# ProPrj_microcontroler_2025-12-02.net
KiCad netlist of a schematic drawn in EasyEDA Pro
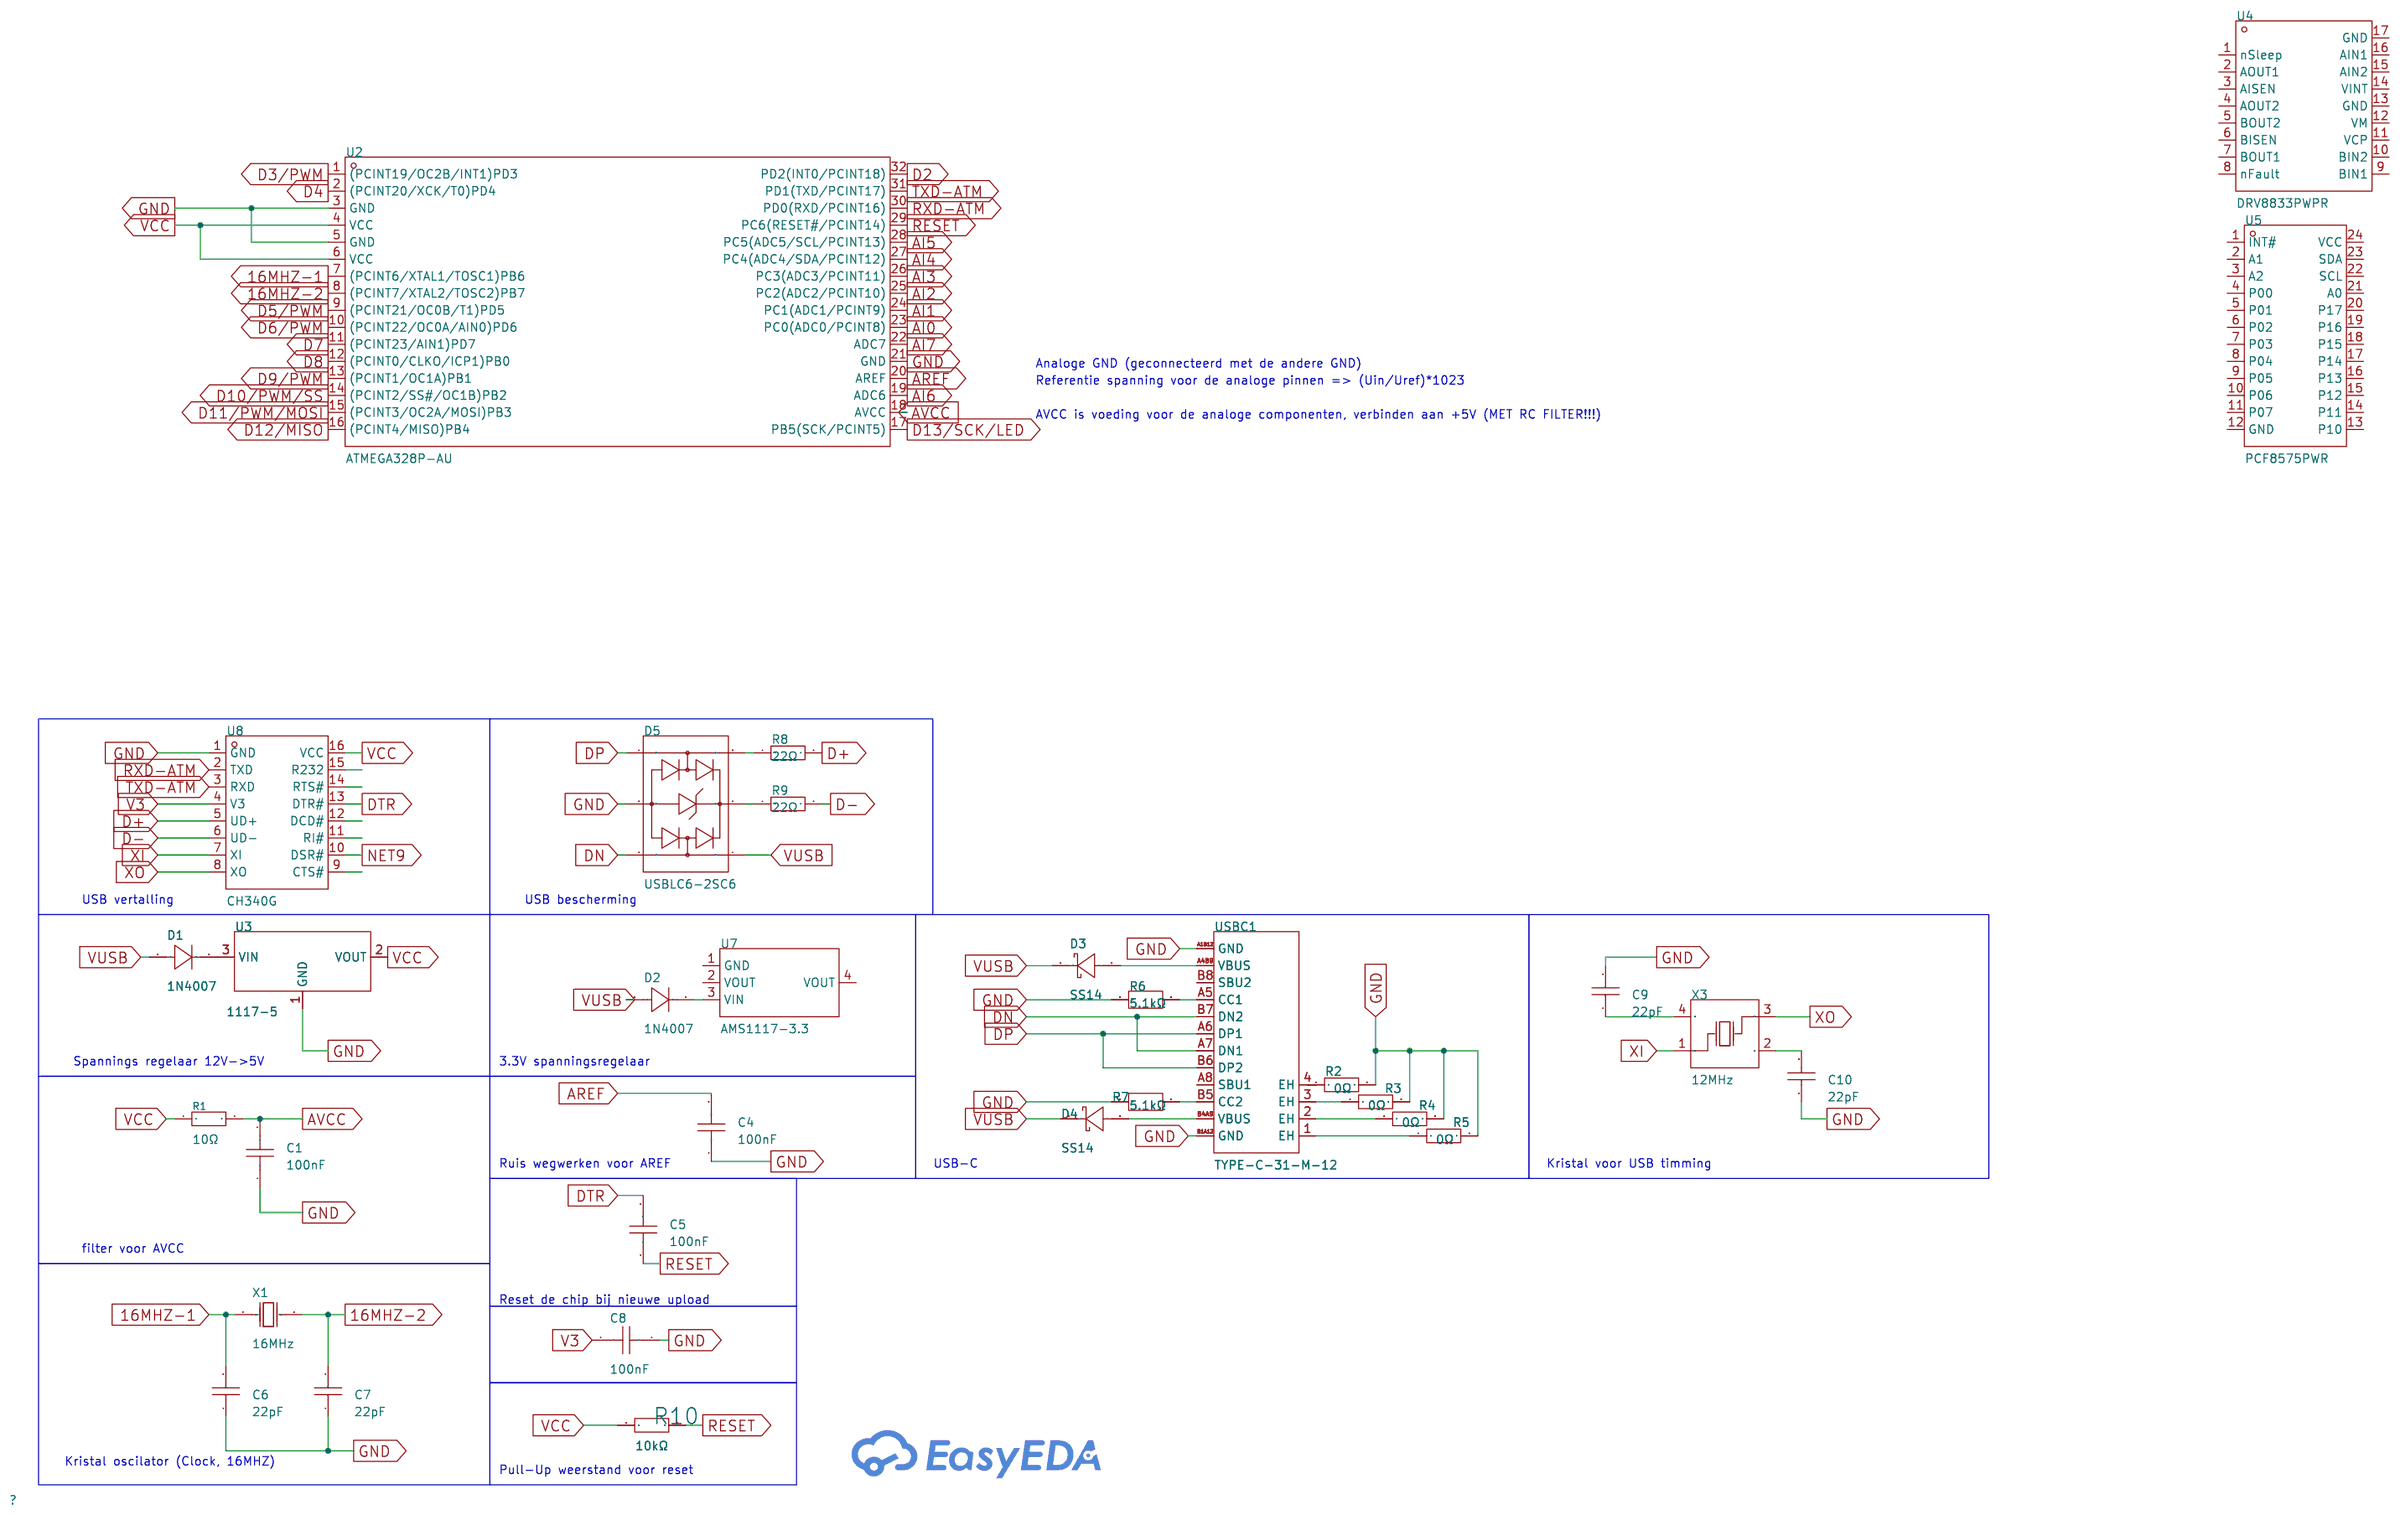
[diagram p0: schematic sheet]

(export (version "E")
  (design (tool "Eeschema 10.0.6"))
  (components
    (comp (ref "C1")
      (value "100nF")
      (footprint "easyedapro:C0603")
      (description "Capacitance:100nF Tolerance:±10% Tolerance:±10% Voltage Rating:50V Temperature Coefficient:X7R")
      (fields
        (field (name "Manufacturer Part") "CC0603KRX7R9BB104")
        (field (name "Manufacturer") "YAGEO(国巨)")
      )
      (libsource (lib "easyedapro") (part "CC0603KRX7R9BB104"))
    )
    (comp (ref "C4")
      (value "100nF")
      (footprint "easyedapro:C0603")
      (description "Capacitance:100nF Tolerance:±10% Tolerance:±10% Voltage Rating:50V Temperature Coefficient:X7R")
      (fields
        (field (name "Manufacturer Part") "CC0603KRX7R9BB104")
        (field (name "Manufacturer") "YAGEO(国巨)")
      )
      (libsource (lib "easyedapro") (part "CC0603KRX7R9BB104"))
    )
    (comp (ref "C5")
      (value "100nF")
      (footprint "easyedapro:C0603")
      (description "Capacitance:100nF Tolerance:±10% Tolerance:±10% Voltage Rating:50V Temperature Coefficient:X7R")
      (fields
        (field (name "Manufacturer Part") "CC0603KRX7R9BB104")
        (field (name "Manufacturer") "YAGEO(国巨)")
      )
      (libsource (lib "easyedapro") (part "CC0603KRX7R9BB104"))
    )
    (comp (ref "C6")
      (value "22pF")
      (footprint "easyedapro:C0402")
      (fields (field (name "Manufacturer Part") "0402CG220J500NT") (field (name "Manufacturer") "FH(风华)"))
      (libsource (lib "easyedapro") (part "0402CG220J500NT"))
    )
    (comp (ref "C7")
      (value "22pF")
      (footprint "easyedapro:C0402")
      (fields (field (name "Manufacturer Part") "0402CG220J500NT") (field (name "Manufacturer") "FH(风华)"))
      (libsource (lib "easyedapro") (part "0402CG220J500NT"))
    )
    (comp (ref "C8")
      (value "100nF")
      (footprint "easyedapro:C0603")
      (description "Capacitance:100nF Tolerance:±10% Tolerance:±10% Voltage Rating:50V Temperature Coefficient:X7R")
      (fields
        (field (name "Manufacturer Part") "CC0603KRX7R9BB104")
        (field (name "Manufacturer") "YAGEO(国巨)")
      )
      (libsource (lib "easyedapro") (part "CC0603KRX7R9BB104"))
    )
    (comp (ref "C9")
      (value "22pF")
      (footprint "easyedapro:C0402")
      (fields (field (name "Manufacturer Part") "0402CG220J500NT") (field (name "Manufacturer") "FH(风华)"))
      (libsource (lib "easyedapro") (part "0402CG220J500NT"))
    )
    (comp (ref "C10")
      (value "22pF")
      (footprint "easyedapro:C0402")
      (fields (field (name "Manufacturer Part") "0402CG220J500NT") (field (name "Manufacturer") "FH(风华)"))
      (libsource (lib "easyedapro") (part "0402CG220J500NT"))
    )
    (comp (ref "D1")
      (value "1N4007")
      (footprint "easyedapro:SMA_L4.3-W2.5-LS5.0-RD")
      (fields (field (name "Manufacturer") "TWGMC(迪嘉)"))
      (libsource (lib "easyedapro") (part "1N4007_C727081"))
    )
    (comp (ref "D2")
      (value "1N4007")
      (footprint "easyedapro:SMA_L4.3-W2.5-LS5.0-RD")
      (fields (field (name "Manufacturer") "TWGMC(迪嘉)"))
      (libsource (lib "easyedapro") (part "1N4007_C727081"))
    )
    (comp (ref "D3")
      (value "SS14")
      (footprint "easyedapro:SMA_L4.3-W2.6-LS5.0-RD")
      (fields (field (name "Manufacturer") "YONGYUTAI(永裕泰)"))
      (libsource (lib "easyedapro") (part "SS14_C47147601"))
    )
    (comp (ref "D4")
      (value "SS14")
      (footprint "easyedapro:SMA_L4.3-W2.6-LS5.0-RD")
      (fields (field (name "Manufacturer") "YONGYUTAI(永裕泰)"))
      (libsource (lib "easyedapro") (part "SS14_C47147601"))
    )
    (comp (ref "D5")
      (value "USBLC6-2SC6")
      (footprint "easyedapro:SOT-23-6_L2.9-W1.6-P0.95-LS2.8-BL")
      (fields (field (name "Manufacturer") "GOODWORK(固得沃克)"))
      (libsource (lib "easyedapro") (part "USBLC6-2SC6_C21713975"))
    )
    (comp (ref "R1")
      (value "10Ω")
      (footprint "easyedapro:R0402")
      (fields
        (field (name "Manufacturer Part") "0402WGF100JTCE")
        (field (name "Manufacturer") "UNI-ROYAL(厚声)")
      )
      (libsource (lib "easyedapro") (part "0402WGF100JTCE"))
    )
    (comp (ref "R2")
      (value "0Ω")
      (footprint "easyedapro:R0603")
      (fields
        (field (name "Manufacturer Part") "0603WAF0000T5E")
        (field (name "Manufacturer") "UNI-ROYAL(厚声)")
      )
      (libsource (lib "easyedapro") (part "0603WAF0000T5E"))
    )
    (comp (ref "R3")
      (value "0Ω")
      (footprint "easyedapro:R0603")
      (fields
        (field (name "Manufacturer Part") "0603WAF0000T5E")
        (field (name "Manufacturer") "UNI-ROYAL(厚声)")
      )
      (libsource (lib "easyedapro") (part "0603WAF0000T5E"))
    )
    (comp (ref "R4")
      (value "0Ω")
      (footprint "easyedapro:R0603")
      (fields
        (field (name "Manufacturer Part") "0603WAF0000T5E")
        (field (name "Manufacturer") "UNI-ROYAL(厚声)")
      )
      (libsource (lib "easyedapro") (part "0603WAF0000T5E"))
    )
    (comp (ref "R5")
      (value "0Ω")
      (footprint "easyedapro:R0603")
      (fields
        (field (name "Manufacturer Part") "0603WAF0000T5E")
        (field (name "Manufacturer") "UNI-ROYAL(厚声)")
      )
      (libsource (lib "easyedapro") (part "0603WAF0000T5E"))
    )
    (comp (ref "R6")
      (value "5.1kΩ")
      (footprint "easyedapro:R0603")
      (fields (field (name "Manufacturer Part") "FRC0603F5101TS") (field (name "Manufacturer") "FOJAN(富捷)"))
      (libsource (lib "easyedapro") (part "FRC0603F5101TS"))
    )
    (comp (ref "R7")
      (value "5.1kΩ")
      (footprint "easyedapro:R0603")
      (fields (field (name "Manufacturer Part") "FRC0603F5101TS") (field (name "Manufacturer") "FOJAN(富捷)"))
      (libsource (lib "easyedapro") (part "FRC0603F5101TS"))
    )
    (comp (ref "R8")
      (value "22Ω")
      (footprint "easyedapro:R0603")
      (fields
        (field (name "Manufacturer Part") "0603WAF220JT5E")
        (field (name "Manufacturer") "UNI-ROYAL(厚声)")
      )
      (libsource (lib "easyedapro") (part "0603WAF220JT5E"))
    )
    (comp (ref "R9")
      (value "22Ω")
      (footprint "easyedapro:R0603")
      (fields
        (field (name "Manufacturer Part") "0603WAF220JT5E")
        (field (name "Manufacturer") "UNI-ROYAL(厚声)")
      )
      (libsource (lib "easyedapro") (part "0603WAF220JT5E"))
    )
    (comp (ref "R10")
      (value "10kΩ")
      (footprint "easyedapro:R0603")
      (fields
        (field (name "Manufacturer Part") "0603WAF1002T5E")
        (field (name "Manufacturer") "UNI-ROYAL(厚声)")
      )
      (libsource (lib "easyedapro") (part "0603WAF1002T5E"))
    )
    (comp (ref "U2")
      (value "ATMEGA328P-AU")
      (footprint "easyedapro:TQFP-32_L7.0-W7.0-P0.80-LS9.0-BL")
      (fields (field (name "Manufacturer") "MICROCHIP(美国微芯)"))
      (libsource (lib "easyedapro") (part "ATMEGA328P-AU"))
    )
    (comp (ref "U3")
      (value "1117-5")
      (footprint "easyedapro:SOT-223-3_L6.5-W3.4-P2.30-LS7.0-BR-1")
      (fields (field (name "Manufacturer") "IDCHIP(英锐芯)"))
      (libsource (lib "easyedapro") (part "1117-5"))
    )
    (comp (ref "U4")
      (value "DRV8833PWPR")
      (footprint "easyedapro:TSSOP-16_L5.0-W4.4-P0.65-LS6.4-BL-EP")
      (description "Technology:Yes Operating Temperature:-40°C~+85°C Operating Temperature:-40°C~+85°C")
      (fields (field (name "Manufacturer") "TI(德州仪器)"))
      (libsource (lib "easyedapro") (part "DRV8833PWP"))
    )
    (comp (ref "U5")
      (value "PCF8575PWR")
      (footprint "easyedapro:TSSOP-24_L7.8-W4.4-P0.65-LS6.4-BL")
      (fields (field (name "Manufacturer") "TI(德州仪器)"))
      (libsource (lib "easyedapro") (part "PCF8575PWR"))
    )
    (comp (ref "U7")
      (value "AMS1117-3.3")
      (footprint "easyedapro:SOT-223-3_L6.5-W3.4-P2.30-LS7.0-BR")
      (fields (field (name "Manufacturer") "AMS"))
      (libsource (lib "easyedapro") (part "AMS1117-3.3"))
    )
    (comp (ref "U8")
      (value "CH340G")
      (footprint "easyedapro:SOIC-16_L9.9-W3.9-P1.27-LS6.0-BL")
      (fields (field (name "Manufacturer") "WCH(南京沁恒)"))
      (libsource (lib "easyedapro") (part "CH340G"))
    )
    (comp (ref "USBC1")
      (value "TYPE-C-31-M-12")
      (footprint "easyedapro:USB-C_SMD-TYPE-C-31-M-12_1")
      (fields (field (name "Manufacturer") "韩国韩荣"))
      (libsource (lib "easyedapro") (part "TYPE-C-31-M-12"))
    )
    (comp (ref "X1")
      (value "16MHz")
      (footprint "easyedapro:HC-49S_L11.4-W4.8")
      (fields (field (name "Manufacturer Part") "X49SM16MSD2SC") (field (name "Manufacturer") "YXC(扬兴晶振)"))
      (libsource (lib "easyedapro") (part "X49SM16MSD2SC"))
    )
    (comp (ref "X3")
      (value "12MHz")
      (footprint "easyedapro:CRYSTAL-SMD_4P-L3.2-W2.5-BL")
      (fields (field (name "Manufacturer Part") "X322512MSB4SI") (field (name "Manufacturer") "YXC(扬兴晶振)"))
      (libsource (lib "easyedapro") (part "X322512MSB4SI"))
    )
  )
  (nets
    (net (code "1") (name "16MHZ-1") (class "Default")
      (node (ref "C6") (pin "2") (pinfunction "2_2") (pintype "input"))
      (node (ref "U2") (pin "7") (pinfunction "(PCINT6/XTAL1/TOSC1)PB6_7") (pintype "unspecified"))
      (node (ref "X1") (pin "1") (pinfunction "OSC1_1") (pintype "input"))
    )
    (net (code "2") (name "16MHZ-2") (class "Default")
      (node (ref "C7") (pin "2") (pinfunction "2_2") (pintype "input"))
      (node (ref "U2") (pin "8") (pinfunction "(PCINT7/XTAL2/TOSC2)PB7_8") (pintype "unspecified"))
      (node (ref "X1") (pin "2") (pinfunction "OSC2_2") (pintype "input"))
    )
    (net (code "3") (name "AI0") (class "Default")
      (node (ref "U2") (pin "23") (pinfunction "PC0(ADC0/PCINT8)_23") (pintype "unspecified"))
    )
    (net (code "4") (name "AI1") (class "Default")
      (node (ref "U2") (pin "24") (pinfunction "PC1(ADC1/PCINT9)_24") (pintype "unspecified"))
    )
    (net (code "5") (name "AI2") (class "Default")
      (node (ref "U2") (pin "25") (pinfunction "PC2(ADC2/PCINT10)_25") (pintype "unspecified"))
    )
    (net (code "6") (name "AI3") (class "Default")
      (node (ref "U2") (pin "26") (pinfunction "PC3(ADC3/PCINT11)_26") (pintype "unspecified"))
    )
    (net (code "7") (name "AI4") (class "Default")
      (node (ref "U2") (pin "27") (pinfunction "PC4(ADC4/SDA/PCINT12)_27") (pintype "unspecified"))
    )
    (net (code "8") (name "AI5") (class "Default")
      (node (ref "U2") (pin "28") (pinfunction "PC5(ADC5/SCL/PCINT13)_28") (pintype "unspecified"))
    )
    (net (code "9") (name "AI6") (class "Default")
      (node (ref "U2") (pin "19") (pinfunction "ADC6_19") (pintype "unspecified"))
    )
    (net (code "10") (name "AI7") (class "Default")
      (node (ref "U2") (pin "22") (pinfunction "ADC7_22") (pintype "unspecified"))
    )
    (net (code "11") (name "AREF") (class "Default")
      (node (ref "C4") (pin "2") (pinfunction "2_2") (pintype "unspecified"))
      (node (ref "U2") (pin "20") (pinfunction "AREF_20") (pintype "unspecified"))
    )
    (net (code "12") (name "AVCC") (class "Default")
      (node (ref "C1") (pin "2") (pinfunction "2_2") (pintype "unspecified"))
      (node (ref "R1") (pin "2") (pinfunction "2_2") (pintype "input"))
      (node (ref "U2") (pin "18") (pinfunction "AVCC_18") (pintype "unspecified"))
    )
    (net (code "13") (name "D+") (class "Default")
      (node (ref "R8") (pin "2") (pinfunction "2_2") (pintype "input"))
      (node (ref "U8") (pin "5") (pinfunction "UD+_5") (pintype "unspecified"))
    )
    (net (code "14") (name "D-") (class "Default")
      (node (ref "R9") (pin "2") (pinfunction "2_2") (pintype "input"))
      (node (ref "U8") (pin "6") (pinfunction "UD-_6") (pintype "unspecified"))
    )
    (net (code "15") (name "D2") (class "Default")
      (node (ref "U2") (pin "32") (pinfunction "PD2(INT0/PCINT18)_32") (pintype "unspecified"))
    )
    (net (code "16") (name "D3{slash}PWM") (class "Default")
      (node (ref "U2") (pin "1") (pinfunction "(PCINT19/OC2B/INT1)PD3_1") (pintype "unspecified"))
    )
    (net (code "17") (name "D4") (class "Default")
      (node (ref "U2") (pin "2") (pinfunction "(PCINT20/XCK/T0)PD4_2") (pintype "unspecified"))
    )
    (net (code "18") (name "D5{slash}PWM") (class "Default")
      (node (ref "U2") (pin "9") (pinfunction "(PCINT21/OC0B/T1)PD5_9") (pintype "unspecified"))
    )
    (net (code "19") (name "D6{slash}PWM") (class "Default")
      (node (ref "U2") (pin "10") (pinfunction "(PCINT22/OC0A/AIN0)PD6_10") (pintype "unspecified"))
    )
    (net (code "20") (name "D7") (class "Default")
      (node (ref "U2") (pin "11") (pinfunction "(PCINT23/AIN1)PD7_11") (pintype "unspecified"))
    )
    (net (code "21") (name "D8") (class "Default")
      (node (ref "U2") (pin "12") (pinfunction "(PCINT0/CLKO/ICP1)PB0_12") (pintype "unspecified"))
    )
    (net (code "22") (name "D9{slash}PWM") (class "Default")
      (node (ref "U2") (pin "13") (pinfunction "(PCINT1/OC1A)PB1_13") (pintype "unspecified"))
    )
    (net (code "23") (name "D10{slash}PWM{slash}SS") (class "Default")
      (node (ref "U2") (pin "14") (pinfunction "(PCINT2/SS#/OC1B)PB2_14") (pintype "unspecified"))
    )
    (net (code "24") (name "D11{slash}PWM{slash}MOSI") (class "Default")
      (node (ref "U2") (pin "15") (pinfunction "(PCINT3/OC2A/MOSI)PB3_15") (pintype "unspecified"))
    )
    (net (code "25") (name "D12{slash}MISO") (class "Default")
      (node (ref "U2") (pin "16") (pinfunction "(PCINT4/MISO)PB4_16") (pintype "unspecified"))
    )
    (net (code "26") (name "D13{slash}SCK{slash}LED") (class "Default")
      (node (ref "U2") (pin "17") (pinfunction "PB5(SCK/PCINT5)_17") (pintype "unspecified"))
    )
    (net (code "27") (name "DN") (class "Default")
      (node (ref "D5") (pin "3") (pinfunction "I/O2_3") (pintype "unspecified"))
      (node (ref "USBC1") (pin "A7") (pinfunction "DN1_A7") (pintype "unspecified"))
      (node (ref "USBC1") (pin "B7") (pinfunction "DN2_B7") (pintype "unspecified"))
    )
    (net (code "28") (name "DP") (class "Default")
      (node (ref "D5") (pin "1") (pinfunction "I/O1_1") (pintype "unspecified"))
      (node (ref "USBC1") (pin "A6") (pinfunction "DP1_A6") (pintype "unspecified"))
      (node (ref "USBC1") (pin "B6") (pinfunction "DP2_B6") (pintype "unspecified"))
    )
    (net (code "29") (name "DTR") (class "Default")
      (node (ref "C5") (pin "2") (pinfunction "2_2") (pintype "unspecified"))
      (node (ref "U8") (pin "13") (pinfunction "DTR#_13") (pintype "unspecified"))
    )
    (net (code "30") (name "GND") (class "Default")
      (node (ref "C1") (pin "1") (pinfunction "1_1") (pintype "unspecified"))
      (node (ref "C10") (pin "1") (pinfunction "1_1") (pintype "input"))
      (node (ref "C4") (pin "1") (pinfunction "1_1") (pintype "unspecified"))
      (node (ref "C6") (pin "1") (pinfunction "1_1") (pintype "input"))
      (node (ref "C7") (pin "1") (pinfunction "1_1") (pintype "input"))
      (node (ref "C8") (pin "1") (pinfunction "1_1") (pintype "unspecified"))
      (node (ref "C9") (pin "2") (pinfunction "2_2") (pintype "input"))
      (node (ref "D5") (pin "2") (pinfunction "GND_2") (pintype "unspecified"))
      (node (ref "R2") (pin "2") (pinfunction "2_2") (pintype "input"))
      (node (ref "R3") (pin "2") (pinfunction "2_2") (pintype "input"))
      (node (ref "R4") (pin "2") (pinfunction "2_2") (pintype "input"))
      (node (ref "R5") (pin "2") (pinfunction "2_2") (pintype "input"))
      (node (ref "R6") (pin "1") (pinfunction "1_1") (pintype "unspecified"))
      (node (ref "R7") (pin "1") (pinfunction "1_1") (pintype "unspecified"))
      (node (ref "U2") (pin "21") (pinfunction "GND_21") (pintype "unspecified"))
      (node (ref "U2") (pin "3") (pinfunction "GND_3") (pintype "unspecified"))
      (node (ref "U2") (pin "5") (pinfunction "GND_5") (pintype "unspecified"))
      (node (ref "U3") (pin "1") (pinfunction "GND_1") (pintype "unspecified"))
      (node (ref "U8") (pin "1") (pinfunction "GND_1") (pintype "unspecified"))
      (node (ref "USBC1") (pin "A1B12") (pinfunction "GND_A1B12") (pintype "unspecified"))
      (node (ref "USBC1") (pin "B1A12") (pinfunction "GND_B1A12") (pintype "unspecified"))
    )
    (net (code "31") (name "NET9") (class "Default")
      (node (ref "U8") (pin "10") (pinfunction "DSR#_10") (pintype "unspecified"))
    )
    (net (code "32") (name "Net-(C9-Pad1)") (class "Default")
      (node (ref "C9") (pin "1") (pinfunction "1_1") (pintype "input"))
      (node (ref "X3") (pin "4") (pinfunction "GND_4") (pintype "unspecified"))
    )
    (net (code "33") (name "Net-(C10-Pad2)") (class "Default")
      (node (ref "C10") (pin "2") (pinfunction "2_2") (pintype "input"))
      (node (ref "X3") (pin "2") (pinfunction "GND_2") (pintype "unspecified"))
    )
    (net (code "34") (name "Net-(D1-K)") (class "Default")
      (node (ref "D1") (pin "1") (pinfunction "K_1") (pintype "unspecified"))
      (node (ref "U3") (pin "3") (pinfunction "VIN_3") (pintype "unspecified"))
    )
    (net (code "35") (name "Net-(D2-K)") (class "Default")
      (node (ref "D2") (pin "1") (pinfunction "K_1") (pintype "unspecified"))
      (node (ref "U7") (pin "3") (pinfunction "VIN_3") (pintype "unspecified"))
    )
    (net (code "36") (name "Net-(D3-A)") (class "Default")
      (node (ref "D3") (pin "2") (pinfunction "A_2") (pintype "unspecified"))
      (node (ref "USBC1") (pin "A4B9") (pinfunction "VBUS_A4B9") (pintype "unspecified"))
    )
    (net (code "37") (name "Net-(D4-A)") (class "Default")
      (node (ref "D4") (pin "2") (pinfunction "A_2") (pintype "unspecified"))
      (node (ref "USBC1") (pin "B4A9") (pinfunction "VBUS_B4A9") (pintype "unspecified"))
    )
    (net (code "38") (name "Net-(D5-I{slash}O1-Pad6)") (class "Default")
      (node (ref "D5") (pin "6") (pinfunction "I/O1_6") (pintype "unspecified"))
      (node (ref "R8") (pin "1") (pinfunction "1_1") (pintype "input"))
    )
    (net (code "39") (name "Net-(D5-VBUS)") (class "Default")
      (node (ref "D5") (pin "5") (pinfunction "VBUS_5") (pintype "unspecified"))
      (node (ref "R9") (pin "1") (pinfunction "1_1") (pintype "input"))
    )
    (net (code "40") (name "Net-(R2-Pad1)") (class "Default")
      (node (ref "R2") (pin "1") (pinfunction "1_1") (pintype "input"))
      (node (ref "USBC1") (pin "4") (pinfunction "EH_4") (pintype "unspecified"))
    )
    (net (code "41") (name "Net-(R3-Pad1)") (class "Default")
      (node (ref "R3") (pin "1") (pinfunction "1_1") (pintype "input"))
      (node (ref "USBC1") (pin "3") (pinfunction "EH_3") (pintype "unspecified"))
    )
    (net (code "42") (name "Net-(R4-Pad1)") (class "Default")
      (node (ref "R4") (pin "1") (pinfunction "1_1") (pintype "input"))
      (node (ref "USBC1") (pin "2") (pinfunction "EH_2") (pintype "unspecified"))
    )
    (net (code "43") (name "Net-(R5-Pad1)") (class "Default")
      (node (ref "R5") (pin "1") (pinfunction "1_1") (pintype "input"))
      (node (ref "USBC1") (pin "1") (pinfunction "EH_1") (pintype "unspecified"))
    )
    (net (code "44") (name "Net-(USBC1-CC1)") (class "Default")
      (node (ref "R6") (pin "2") (pinfunction "2_2") (pintype "unspecified"))
      (node (ref "USBC1") (pin "A5") (pinfunction "CC1_A5") (pintype "unspecified"))
    )
    (net (code "45") (name "Net-(USBC1-CC2)") (class "Default")
      (node (ref "R7") (pin "2") (pinfunction "2_2") (pintype "unspecified"))
      (node (ref "USBC1") (pin "B5") (pinfunction "CC2_B5") (pintype "unspecified"))
    )
    (net (code "46") (name "RESET") (class "Default")
      (node (ref "C5") (pin "1") (pinfunction "1_1") (pintype "unspecified"))
      (node (ref "R10") (pin "2") (pinfunction "2_2") (pintype "input"))
      (node (ref "U2") (pin "29") (pinfunction "PC6(RESET#/PCINT14)_29") (pintype "unspecified"))
    )
    (net (code "47") (name "RXD-ATM") (class "Default")
      (node (ref "U2") (pin "30") (pinfunction "PD0(RXD/PCINT16)_30") (pintype "unspecified"))
      (node (ref "U8") (pin "2") (pinfunction "TXD_2") (pintype "unspecified"))
    )
    (net (code "48") (name "TXD-ATM") (class "Default")
      (node (ref "U2") (pin "31") (pinfunction "PD1(TXD/PCINT17)_31") (pintype "unspecified"))
      (node (ref "U8") (pin "3") (pinfunction "RXD_3") (pintype "unspecified"))
    )
    (net (code "49") (name "V3") (class "Default")
      (node (ref "C8") (pin "2") (pinfunction "2_2") (pintype "unspecified"))
      (node (ref "U8") (pin "4") (pinfunction "V3_4") (pintype "unspecified"))
    )
    (net (code "50") (name "VCC") (class "Default")
      (node (ref "R1") (pin "1") (pinfunction "1_1") (pintype "input"))
      (node (ref "R10") (pin "1") (pinfunction "1_1") (pintype "input"))
      (node (ref "U2") (pin "4") (pinfunction "VCC_4") (pintype "unspecified"))
      (node (ref "U2") (pin "6") (pinfunction "VCC_6") (pintype "unspecified"))
      (node (ref "U3") (pin "2") (pinfunction "VOUT_2") (pintype "unspecified"))
      (node (ref "U8") (pin "16") (pinfunction "VCC_16") (pintype "unspecified"))
    )
    (net (code "51") (name "VUSB") (class "Default")
      (node (ref "D1") (pin "2") (pinfunction "A_2") (pintype "unspecified"))
      (node (ref "D2") (pin "2") (pinfunction "A_2") (pintype "unspecified"))
      (node (ref "D3") (pin "1") (pinfunction "C_1") (pintype "unspecified"))
      (node (ref "D4") (pin "1") (pinfunction "C_1") (pintype "unspecified"))
      (node (ref "D5") (pin "4") (pinfunction "I/O2_4") (pintype "unspecified"))
    )
    (net (code "52") (name "XI") (class "Default")
      (node (ref "U8") (pin "7") (pinfunction "XI_7") (pintype "unspecified"))
      (node (ref "X3") (pin "1") (pinfunction "OSC1_1") (pintype "unspecified"))
    )
    (net (code "53") (name "XO") (class "Default")
      (node (ref "U8") (pin "8") (pinfunction "XO_8") (pintype "unspecified"))
      (node (ref "X3") (pin "3") (pinfunction "OSC2_3") (pintype "unspecified"))
    )
    (net (code "54") (name "unconnected-(U4-AIN1-Pad16)") (class "Default")
      (node (ref "U4") (pin "16") (pinfunction "AIN1_16") (pintype "unspecified"))
    )
    (net (code "55") (name "unconnected-(U4-AIN2-Pad15)") (class "Default")
      (node (ref "U4") (pin "15") (pinfunction "AIN2_15") (pintype "unspecified"))
    )
    (net (code "56") (name "unconnected-(U4-AISEN-Pad3)") (class "Default")
      (node (ref "U4") (pin "3") (pinfunction "AISEN_3") (pintype "unspecified"))
    )
    (net (code "57") (name "unconnected-(U4-AOUT1-Pad2)") (class "Default")
      (node (ref "U4") (pin "2") (pinfunction "AOUT1_2") (pintype "unspecified"))
    )
    (net (code "58") (name "unconnected-(U4-AOUT2-Pad4)") (class "Default")
      (node (ref "U4") (pin "4") (pinfunction "AOUT2_4") (pintype "unspecified"))
    )
    (net (code "59") (name "unconnected-(U4-BIN1-Pad9)") (class "Default")
      (node (ref "U4") (pin "9") (pinfunction "BIN1_9") (pintype "unspecified"))
    )
    (net (code "60") (name "unconnected-(U4-BIN2-Pad10)") (class "Default")
      (node (ref "U4") (pin "10") (pinfunction "BIN2_10") (pintype "unspecified"))
    )
    (net (code "61") (name "unconnected-(U4-BISEN-Pad6)") (class "Default")
      (node (ref "U4") (pin "6") (pinfunction "BISEN_6") (pintype "unspecified"))
    )
    (net (code "62") (name "unconnected-(U4-BOUT1-Pad7)") (class "Default")
      (node (ref "U4") (pin "7") (pinfunction "BOUT1_7") (pintype "unspecified"))
    )
    (net (code "63") (name "unconnected-(U4-BOUT2-Pad5)") (class "Default")
      (node (ref "U4") (pin "5") (pinfunction "BOUT2_5") (pintype "unspecified"))
    )
    (net (code "64") (name "unconnected-(U4-GND-Pad13)") (class "Default")
      (node (ref "U4") (pin "13") (pinfunction "GND_13") (pintype "unspecified"))
    )
    (net (code "65") (name "unconnected-(U4-GND-Pad17)") (class "Default")
      (node (ref "U4") (pin "17") (pinfunction "GND_17") (pintype "unspecified"))
    )
    (net (code "66") (name "unconnected-(U4-VCP-Pad11)") (class "Default")
      (node (ref "U4") (pin "11") (pinfunction "VCP_11") (pintype "unspecified"))
    )
    (net (code "67") (name "unconnected-(U4-VINT-Pad14)") (class "Default")
      (node (ref "U4") (pin "14") (pinfunction "VINT_14") (pintype "unspecified"))
    )
    (net (code "68") (name "unconnected-(U4-VM-Pad12)") (class "Default")
      (node (ref "U4") (pin "12") (pinfunction "VM_12") (pintype "unspecified"))
    )
    (net (code "69") (name "unconnected-(U4-nFault-Pad8)") (class "Default")
      (node (ref "U4") (pin "8") (pinfunction "nFault_8") (pintype "unspecified"))
    )
    (net (code "70") (name "unconnected-(U4-nSleep-Pad1)") (class "Default")
      (node (ref "U4") (pin "1") (pinfunction "nSleep_1") (pintype "unspecified"))
    )
    (net (code "71") (name "unconnected-(U5-A0-Pad21)") (class "Default")
      (node (ref "U5") (pin "21") (pinfunction "A0_21") (pintype "unspecified"))
    )
    (net (code "72") (name "unconnected-(U5-A1-Pad2)") (class "Default")
      (node (ref "U5") (pin "2") (pinfunction "A1_2") (pintype "unspecified"))
    )
    (net (code "73") (name "unconnected-(U5-A2-Pad3)") (class "Default")
      (node (ref "U5") (pin "3") (pinfunction "A2_3") (pintype "unspecified"))
    )
    (net (code "74") (name "unconnected-(U5-GND-Pad12)") (class "Default")
      (node (ref "U5") (pin "12") (pinfunction "GND_12") (pintype "unspecified"))
    )
    (net (code "75") (name "unconnected-(U5-INT#-Pad1)") (class "Default")
      (node (ref "U5") (pin "1") (pinfunction "INT#_1") (pintype "unspecified"))
    )
    (net (code "76") (name "unconnected-(U5-P00-Pad4)") (class "Default")
      (node (ref "U5") (pin "4") (pinfunction "P00_4") (pintype "unspecified"))
    )
    (net (code "77") (name "unconnected-(U5-P01-Pad5)") (class "Default")
      (node (ref "U5") (pin "5") (pinfunction "P01_5") (pintype "unspecified"))
    )
    (net (code "78") (name "unconnected-(U5-P02-Pad6)") (class "Default")
      (node (ref "U5") (pin "6") (pinfunction "P02_6") (pintype "unspecified"))
    )
    (net (code "79") (name "unconnected-(U5-P03-Pad7)") (class "Default")
      (node (ref "U5") (pin "7") (pinfunction "P03_7") (pintype "unspecified"))
    )
    (net (code "80") (name "unconnected-(U5-P04-Pad8)") (class "Default")
      (node (ref "U5") (pin "8") (pinfunction "P04_8") (pintype "unspecified"))
    )
    (net (code "81") (name "unconnected-(U5-P05-Pad9)") (class "Default")
      (node (ref "U5") (pin "9") (pinfunction "P05_9") (pintype "unspecified"))
    )
    (net (code "82") (name "unconnected-(U5-P06-Pad10)") (class "Default")
      (node (ref "U5") (pin "10") (pinfunction "P06_10") (pintype "unspecified"))
    )
    (net (code "83") (name "unconnected-(U5-P07-Pad11)") (class "Default")
      (node (ref "U5") (pin "11") (pinfunction "P07_11") (pintype "unspecified"))
    )
    (net (code "84") (name "unconnected-(U5-P10-Pad13)") (class "Default")
      (node (ref "U5") (pin "13") (pinfunction "P10_13") (pintype "unspecified"))
    )
    (net (code "85") (name "unconnected-(U5-P11-Pad14)") (class "Default")
      (node (ref "U5") (pin "14") (pinfunction "P11_14") (pintype "unspecified"))
    )
    (net (code "86") (name "unconnected-(U5-P12-Pad15)") (class "Default")
      (node (ref "U5") (pin "15") (pinfunction "P12_15") (pintype "unspecified"))
    )
    (net (code "87") (name "unconnected-(U5-P13-Pad16)") (class "Default")
      (node (ref "U5") (pin "16") (pinfunction "P13_16") (pintype "unspecified"))
    )
    (net (code "88") (name "unconnected-(U5-P14-Pad17)") (class "Default")
      (node (ref "U5") (pin "17") (pinfunction "P14_17") (pintype "unspecified"))
    )
    (net (code "89") (name "unconnected-(U5-P15-Pad18)") (class "Default")
      (node (ref "U5") (pin "18") (pinfunction "P15_18") (pintype "unspecified"))
    )
    (net (code "90") (name "unconnected-(U5-P16-Pad19)") (class "Default")
      (node (ref "U5") (pin "19") (pinfunction "P16_19") (pintype "unspecified"))
    )
    (net (code "91") (name "unconnected-(U5-P17-Pad20)") (class "Default")
      (node (ref "U5") (pin "20") (pinfunction "P17_20") (pintype "unspecified"))
    )
    (net (code "92") (name "unconnected-(U5-SCL-Pad22)") (class "Default")
      (node (ref "U5") (pin "22") (pinfunction "SCL_22") (pintype "unspecified"))
    )
    (net (code "93") (name "unconnected-(U5-SDA-Pad23)") (class "Default")
      (node (ref "U5") (pin "23") (pinfunction "SDA_23") (pintype "unspecified"))
    )
    (net (code "94") (name "unconnected-(U5-VCC-Pad24)") (class "Default")
      (node (ref "U5") (pin "24") (pinfunction "VCC_24") (pintype "unspecified"))
    )
    (net (code "95") (name "unconnected-(U7-GND-Pad1)") (class "Default")
      (node (ref "U7") (pin "1") (pinfunction "GND_1") (pintype "unspecified"))
    )
    (net (code "96") (name "unconnected-(U7-VOUT-Pad2)") (class "Default")
      (node (ref "U7") (pin "2") (pinfunction "VOUT_2") (pintype "unspecified"))
    )
    (net (code "97") (name "unconnected-(U7-VOUT-Pad4)") (class "Default")
      (node (ref "U7") (pin "4") (pinfunction "VOUT_4") (pintype "unspecified"))
    )
    (net (code "98") (name "unconnected-(U8-CTS#-Pad9)") (class "Default")
      (node (ref "U8") (pin "9") (pinfunction "CTS#_9") (pintype "unspecified"))
    )
    (net (code "99") (name "unconnected-(U8-DCD#-Pad12)") (class "Default")
      (node (ref "U8") (pin "12") (pinfunction "DCD#_12") (pintype "unspecified"))
    )
    (net (code "100") (name "unconnected-(U8-R232-Pad15)") (class "Default")
      (node (ref "U8") (pin "15") (pinfunction "R232_15") (pintype "unspecified"))
    )
    (net (code "101") (name "unconnected-(U8-RI#-Pad11)") (class "Default")
      (node (ref "U8") (pin "11") (pinfunction "RI#_11") (pintype "unspecified"))
    )
    (net (code "102") (name "unconnected-(U8-RTS#-Pad14)") (class "Default")
      (node (ref "U8") (pin "14") (pinfunction "RTS#_14") (pintype "unspecified"))
    )
    (net (code "103") (name "unconnected-(USBC1-SBU1-PadA8)") (class "Default")
      (node (ref "USBC1") (pin "A8") (pinfunction "SBU1_A8") (pintype "unspecified"))
    )
    (net (code "104") (name "unconnected-(USBC1-SBU2-PadB8)") (class "Default")
      (node (ref "USBC1") (pin "B8") (pinfunction "SBU2_B8") (pintype "unspecified"))
    )
  )
)
